# plc_module_xs_00001_001_STM32.net
KiCad netlist of a schematic drawn in Altium Designer
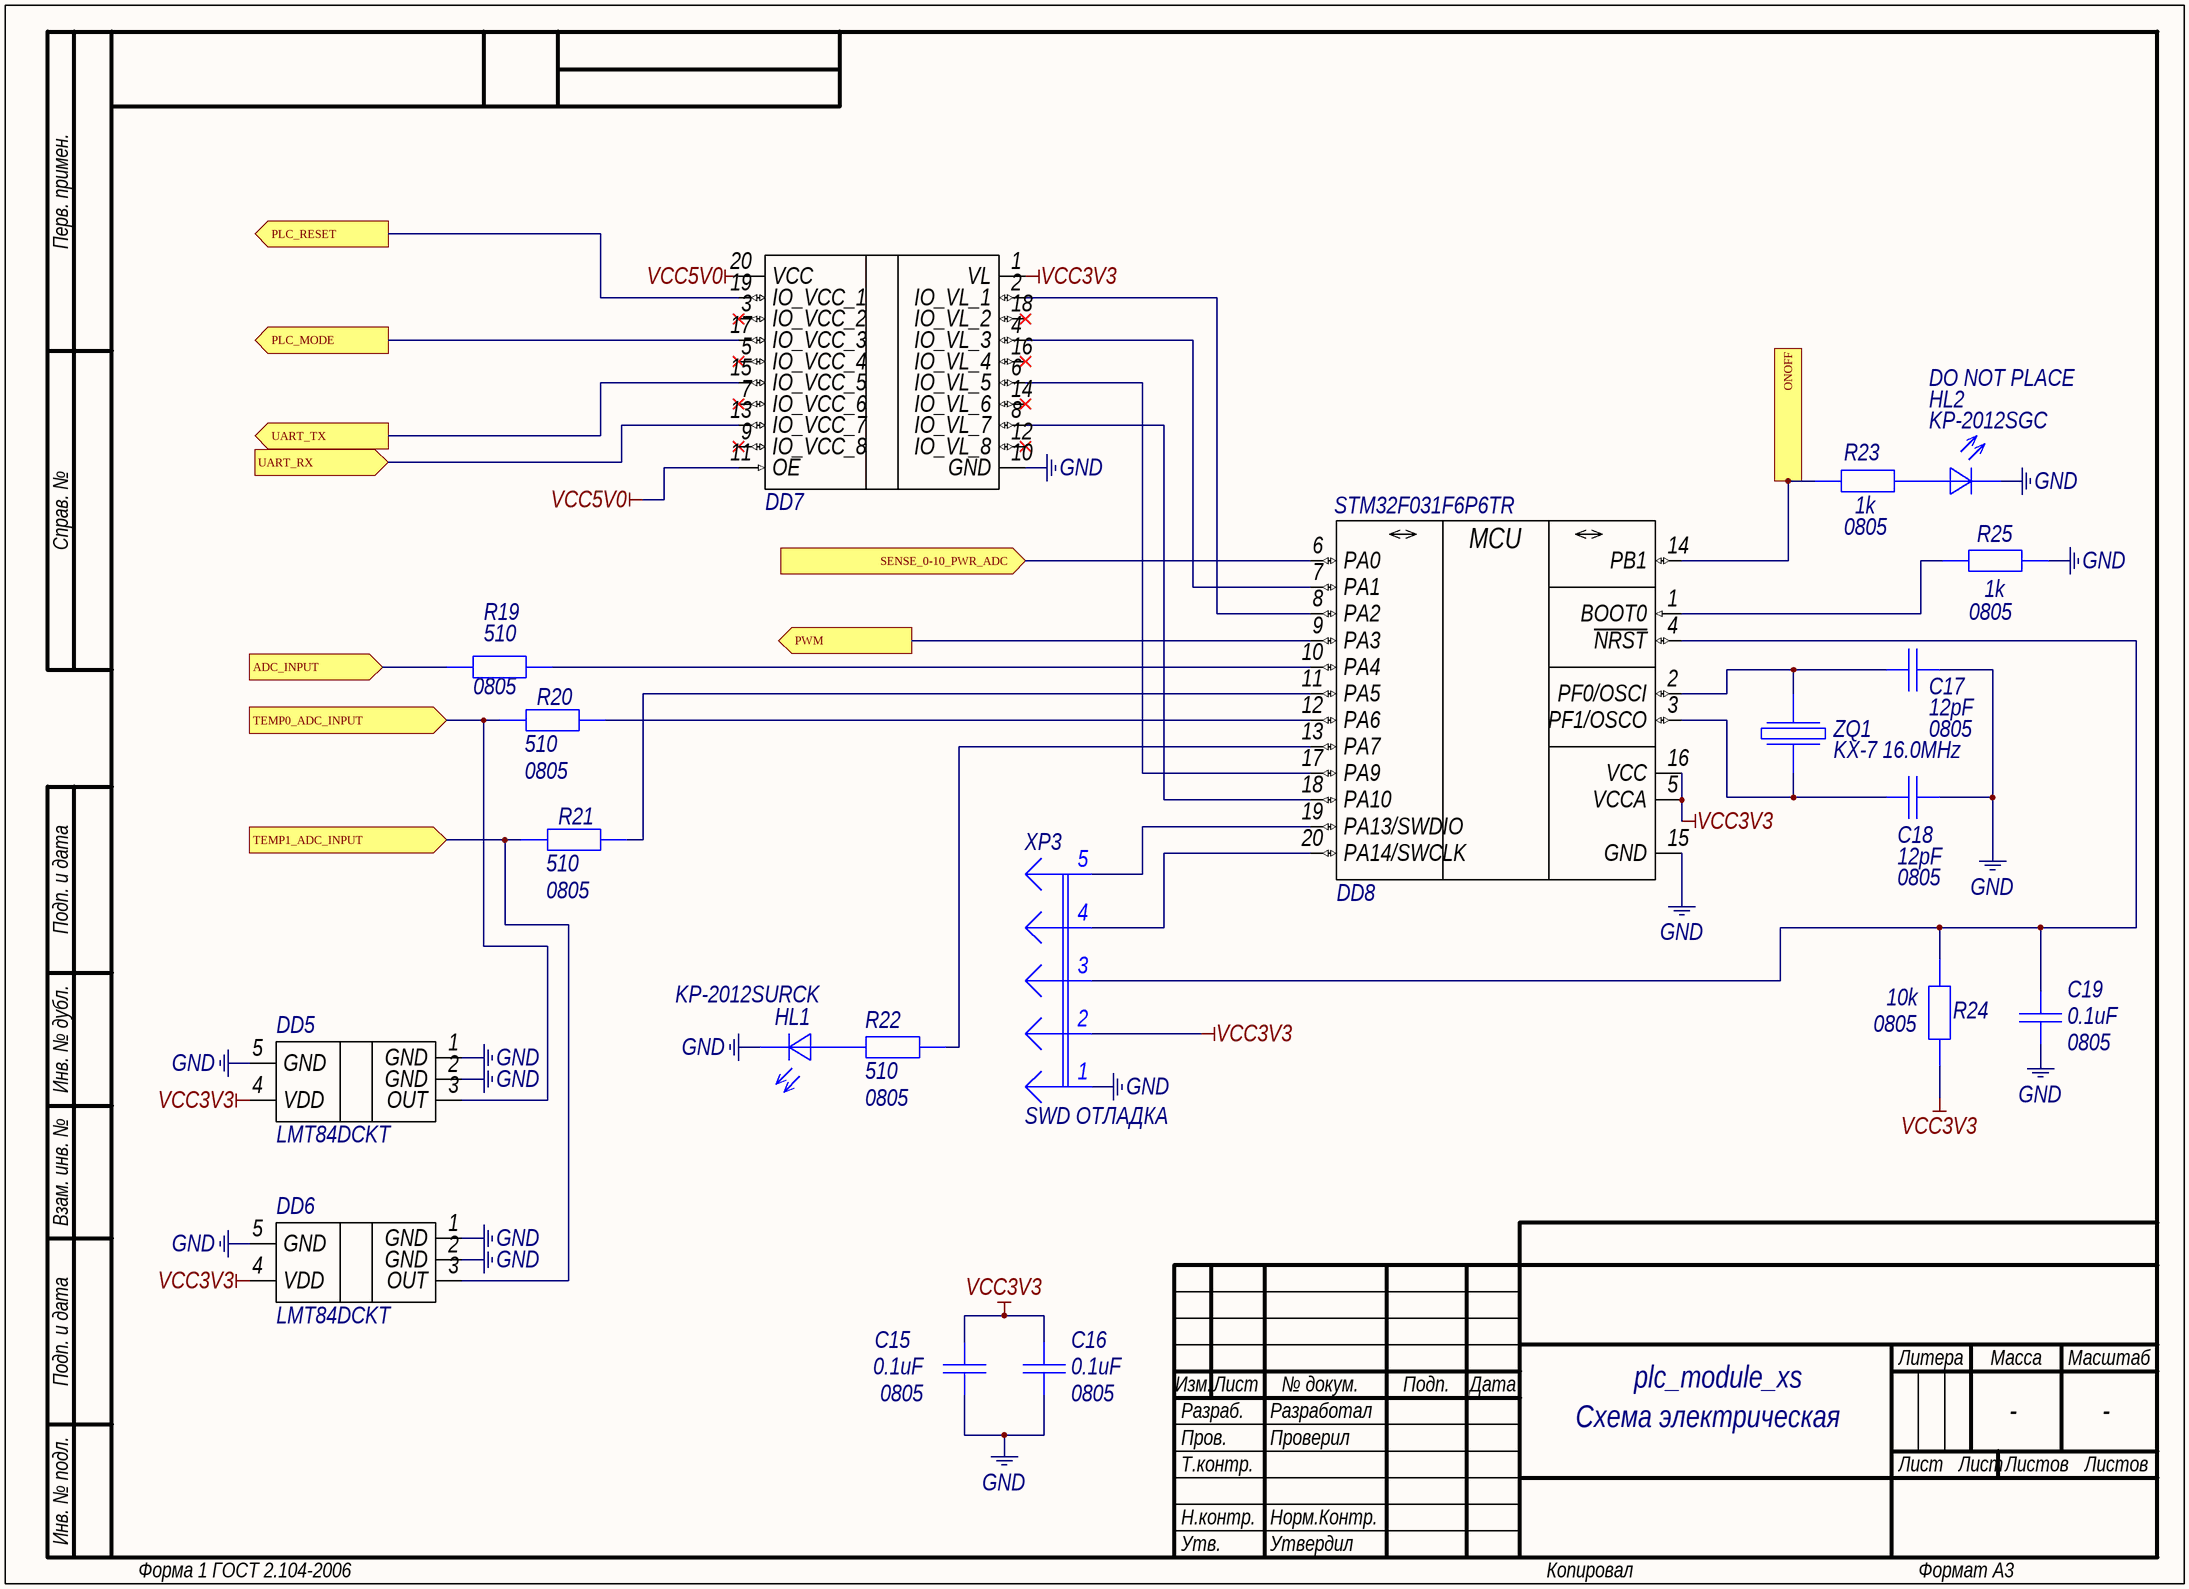
[diagram p0: plc_module_xs.00001.001_STM32.SchDoc]

(export (version "E")
  (design (tool "Eeschema 10.0.6"))
  (components
    (comp (ref "C15")
      (value "0.1uF")
      (footprint "0805")
      (fields
        (field (name "PART NUMBER") "GRM21BR71H104KA01L")
        (field (name "VOLTAGE") "50V")
        (field (name "TOLERANCE") "±10%")
        (field (name "PUBLISHER") "Andrew Danich")
      )
      (libsource (lib "GOST_IMPORT_PARTS") (part "Capacitor"))
    )
    (comp (ref "C16")
      (value "0.1uF")
      (footprint "0805")
      (fields
        (field (name "PART NUMBER") "GRM21BR71H104KA01L")
        (field (name "VOLTAGE") "50V")
        (field (name "TOLERANCE") "±10%")
        (field (name "PUBLISHER") "Andrew Danich")
      )
      (libsource (lib "GOST_IMPORT_PARTS") (part "Capacitor"))
    )
    (comp (ref "C17")
      (value "12pF")
      (footprint "0805")
      (fields
        (field (name "PART NUMBER") "CC0805JRNPO9BN120")
        (field (name "VOLTAGE") "50V")
        (field (name "TOLERANCE") "±5%")
        (field (name "PUBLISHER") "Andrew Danich")
      )
      (libsource (lib "GOST_IMPORT_PARTS") (part "Capacitor"))
    )
    (comp (ref "C18")
      (value "12pF")
      (footprint "0805")
      (fields
        (field (name "PART NUMBER") "CC0805JRNPO9BN120")
        (field (name "VOLTAGE") "50V")
        (field (name "TOLERANCE") "±5%")
        (field (name "PUBLISHER") "Andrew Danich")
      )
      (libsource (lib "GOST_IMPORT_PARTS") (part "Capacitor"))
    )
    (comp (ref "C19")
      (value "0.1uF")
      (footprint "0805")
      (fields
        (field (name "PART NUMBER") "GRM21BR71H104KA01L")
        (field (name "VOLTAGE") "50V")
        (field (name "TOLERANCE") "±10%")
        (field (name "PUBLISHER") "Andrew Danich")
      )
      (libsource (lib "GOST_IMPORT_PARTS") (part "Capacitor"))
    )
    (comp (ref "DD5")
      (value "LMT84DCKT")
      (footprint "SOT65P210X110-5N")
      (description "LMT84/LMT84-Q1 1.5V, SC70/TO-92/TO-126,Analog Temperature Sensors with Class-AB Output")
      (fields (field (name "MANUFACTURER") "Texas Instruments"))
      (libsource (lib "GOST_IMPORT_PARTS") (part "LMT84DCKT"))
    )
    (comp (ref "DD6")
      (value "LMT84DCKT")
      (footprint "SOT65P210X110-5N")
      (description "LMT84/LMT84-Q1 1.5V, SC70/TO-92/TO-126,Analog Temperature Sensors with Class-AB Output")
      (fields (field (name "MANUFACTURER") "Texas Instruments"))
      (libsource (lib "GOST_IMPORT_PARTS") (part "LMT84DCKT"))
    )
    (comp (ref "DD7")
      (value "ST2378ETTR")
      (footprint "SOP65P640X120-20N")
      (description "8-bit dual supply 1.71 V to 5.5 V level translator with I/O VCC ±15 kV ESD protection")
      (fields (field (name "MANUFACTURER") "STMicroelectronics") (field (name "PUBLISHER") "Andrew Danich"))
      (libsource (lib "GOST_IMPORT_PARTS") (part "ST2378ETTR"))
    )
    (comp (ref "DD8")
      (value "STM32F031F6P6TR")
      (footprint "STM-TSSOP20_N")
      (fields (field (name "MANUFACTURER") "STMicroelectronics") (field (name "PUBLISHER") "Andrew Danich"))
      (libsource (lib "GOST_IMPORT_PARTS") (part "STM32F031Fxxx-Series"))
    )
    (comp (ref "HL1")
      (value "KP-2012SURCK")
      (footprint "LD0805")
      (fields (field (name "MANUFACTURER") "Kingbright") (field (name "PUBLISHER") "Andrew Danich"))
      (libsource (lib "GOST_IMPORT_PARTS") (part "Led-1"))
    )
    (comp (ref "HL2")
      (value "DO NOT PLACE")
      (footprint "LD0805")
      (fields
        (field (name "PART NUMBER") "KP-2012SGC")
        (field (name "MANUFACTURER") "Kingbright")
        (field (name "PUBLISHER") "Andrew Danich")
      )
      (libsource (lib "GOST_IMPORT_PARTS") (part "Led-1"))
    )
    (comp (ref "R19")
      (value "510")
      (footprint "0805")
      (fields
        (field (name "PART NUMBER") "RC0805JR-07510RL")
        (field (name "TOLERANCE") "±5%")
        (field (name "MANUFACTURER") "Yageo")
        (field (name "PUBLISHER") "Andrew Danich")
      )
      (libsource (lib "GOST_IMPORT_PARTS") (part "Resistor"))
    )
    (comp (ref "R20")
      (value "510")
      (footprint "0805")
      (fields
        (field (name "PART NUMBER") "RC0805JR-07510RL")
        (field (name "TOLERANCE") "±5%")
        (field (name "MANUFACTURER") "Yageo")
        (field (name "PUBLISHER") "Andrew Danich")
      )
      (libsource (lib "GOST_IMPORT_PARTS") (part "Resistor"))
    )
    (comp (ref "R21")
      (value "510")
      (footprint "0805")
      (fields
        (field (name "PART NUMBER") "RC0805JR-07510RL")
        (field (name "TOLERANCE") "±5%")
        (field (name "MANUFACTURER") "Yageo")
        (field (name "PUBLISHER") "Andrew Danich")
      )
      (libsource (lib "GOST_IMPORT_PARTS") (part "Resistor"))
    )
    (comp (ref "R22")
      (value "510")
      (footprint "0805")
      (fields
        (field (name "PART NUMBER") "RC0805JR-07510RL")
        (field (name "TOLERANCE") "±5%")
        (field (name "MANUFACTURER") "Yageo")
        (field (name "PUBLISHER") "Andrew Danich")
      )
      (libsource (lib "GOST_IMPORT_PARTS") (part "Resistor"))
    )
    (comp (ref "R23")
      (value "1k")
      (footprint "0805")
      (fields
        (field (name "PART NUMBER") "RC0805JR-071KL")
        (field (name "TOLERANCE") "±5%")
        (field (name "MANUFACTURER") "Yageo")
        (field (name "PUBLISHER") "Andrew Danich")
      )
      (libsource (lib "GOST_IMPORT_PARTS") (part "Resistor"))
    )
    (comp (ref "R24")
      (value "10k")
      (footprint "0805")
      (fields
        (field (name "PART NUMBER") "RC0805JR-0710KL")
        (field (name "TOLERANCE") "±5%")
        (field (name "MANUFACTURER") "Yageo")
        (field (name "PUBLISHER") "Andrew Danich")
      )
      (libsource (lib "GOST_IMPORT_PARTS") (part "Resistor"))
    )
    (comp (ref "R25")
      (value "1k")
      (footprint "0805")
      (fields
        (field (name "PART NUMBER") "RC0805JR-071KL")
        (field (name "TOLERANCE") "±5%")
        (field (name "MANUFACTURER") "Yageo")
        (field (name "PUBLISHER") "Andrew Danich")
      )
      (libsource (lib "GOST_IMPORT_PARTS") (part "Resistor"))
    )
    (comp (ref "XP3")
      (value "SWD ОТЛАДКА")
      (footprint "PLS-5")
      (fields (field (name "PART NUMBER") "PLS-5") (field (name "PUBLISHER") "Andrew Danich"))
      (libsource (lib "GOST_IMPORT_PARTS") (part "Con-5-M"))
    )
    (comp (ref "ZQ1")
      (value "KX-7 16.0MHz")
      (footprint "SMD 3.2x2.5mm")
      (fields
        (field (name "MANUFACTURER") "GEYER ELECTRONIC")
        (field (name "Comment") "Crystal-1_3p")
        (field (name "PUBLISHER") "Andrew Danich")
      )
      (libsource (lib "GOST_IMPORT_PARTS") (part "Crystal-1_3p"))
    )
  )
  (nets
    (net (code "1") (name "/ADC_INPUT") (class "Default")
      (node (ref "R19") (pin "2") (pinfunction "2_2") (pintype "passive"))
    )
    (net (code "2") (name "/ONOFF") (class "Default")
      (node (ref "DD8") (pin "14") (pinfunction "PB1_14") (pintype "bidirectional"))
      (node (ref "R23") (pin "1") (pinfunction "1_1") (pintype "passive"))
    )
    (net (code "3") (name "/PLC_MODE") (class "Default")
      (node (ref "DD7") (pin "17") (pinfunction "IO_VCC_3_17") (pintype "bidirectional"))
    )
    (net (code "4") (name "/PLC_RESET") (class "Default")
      (node (ref "DD7") (pin "19") (pinfunction "IO_VCC_1_19") (pintype "bidirectional"))
    )
    (net (code "5") (name "/PWM") (class "Default")
      (node (ref "DD8") (pin "9") (pinfunction "PA3_9") (pintype "bidirectional"))
    )
    (net (code "6") (name "/SENSE_0-10_PWR_ADC") (class "Default")
      (node (ref "DD8") (pin "6") (pinfunction "PA0_6") (pintype "bidirectional"))
    )
    (net (code "7") (name "/TEMP0_ADC_INPUT") (class "Default")
      (node (ref "DD5") (pin "3") (pinfunction "OUT_3") (pintype "passive"))
      (node (ref "R20") (pin "2") (pinfunction "2_2") (pintype "passive"))
    )
    (net (code "8") (name "/TEMP1_ADC_INPUT") (class "Default")
      (node (ref "DD6") (pin "3") (pinfunction "OUT_3") (pintype "passive"))
      (node (ref "R21") (pin "2") (pinfunction "2_2") (pintype "passive"))
    )
    (net (code "9") (name "/UART_RX") (class "Default")
      (node (ref "DD7") (pin "13") (pinfunction "IO_VCC_7_13") (pintype "bidirectional"))
    )
    (net (code "10") (name "/UART_TX") (class "Default")
      (node (ref "DD7") (pin "15") (pinfunction "IO_VCC_5_15") (pintype "bidirectional"))
    )
    (net (code "11") (name "GND") (class "Default")
      (node (ref "C15") (pin "2") (pinfunction "2_2") (pintype "passive"))
      (node (ref "C16") (pin "1") (pinfunction "1_1") (pintype "passive"))
      (node (ref "C17") (pin "1") (pinfunction "1_1") (pintype "passive"))
      (node (ref "C18") (pin "1") (pinfunction "1_1") (pintype "passive"))
      (node (ref "C19") (pin "1") (pinfunction "1_1") (pintype "passive"))
      (node (ref "DD5") (pin "1") (pinfunction "GND_1") (pintype "passive"))
      (node (ref "DD5") (pin "2") (pinfunction "GND_2") (pintype "passive"))
      (node (ref "DD5") (pin "5") (pinfunction "GND_5") (pintype "passive"))
      (node (ref "DD6") (pin "1") (pinfunction "GND_1") (pintype "passive"))
      (node (ref "DD6") (pin "2") (pinfunction "GND_2") (pintype "passive"))
      (node (ref "DD6") (pin "5") (pinfunction "GND_5") (pintype "passive"))
      (node (ref "DD7") (pin "10") (pinfunction "GND_10") (pintype "power_in"))
      (node (ref "DD8") (pin "15") (pinfunction "GND_15") (pintype "power_in"))
      (node (ref "HL1") (pin "2") (pinfunction "К_2") (pintype "passive"))
      (node (ref "HL2") (pin "2") (pinfunction "К_2") (pintype "passive"))
      (node (ref "R25") (pin "2") (pinfunction "2_2") (pintype "passive"))
      (node (ref "XP3") (pin "1") (pintype "passive"))
    )
    (net (code "12") (name "Net-(DD7-IO_VL_1)") (class "Default")
      (node (ref "DD7") (pin "2") (pinfunction "IO_VL_1_2") (pintype "bidirectional"))
      (node (ref "DD8") (pin "8") (pinfunction "PA2_8") (pintype "bidirectional"))
    )
    (net (code "13") (name "Net-(DD7-IO_VL_3)") (class "Default")
      (node (ref "DD7") (pin "4") (pinfunction "IO_VL_3_4") (pintype "bidirectional"))
      (node (ref "DD8") (pin "7") (pinfunction "PA1_7") (pintype "bidirectional"))
    )
    (net (code "14") (name "Net-(DD7-IO_VL_5)") (class "Default")
      (node (ref "DD7") (pin "6") (pinfunction "IO_VL_5_6") (pintype "bidirectional"))
      (node (ref "DD8") (pin "17") (pinfunction "PA9_17") (pintype "bidirectional"))
    )
    (net (code "15") (name "Net-(DD7-IO_VL_7)") (class "Default")
      (node (ref "DD7") (pin "8") (pinfunction "IO_VL_7_8") (pintype "bidirectional"))
      (node (ref "DD8") (pin "18") (pinfunction "PA10_18") (pintype "bidirectional"))
    )
    (net (code "16") (name "Net-(DD8-BOOT0)") (class "Default")
      (node (ref "DD8") (pin "1") (pinfunction "BOOT0_1") (pintype "input"))
      (node (ref "R25") (pin "1") (pinfunction "1_1") (pintype "passive"))
    )
    (net (code "17") (name "Net-(DD8-PA4)") (class "Default")
      (node (ref "DD8") (pin "10") (pinfunction "PA4_10") (pintype "bidirectional"))
      (node (ref "R19") (pin "1") (pinfunction "1_1") (pintype "passive"))
    )
    (net (code "18") (name "Net-(DD8-PA5)") (class "Default")
      (node (ref "DD8") (pin "11") (pinfunction "PA5_11") (pintype "bidirectional"))
      (node (ref "R21") (pin "1") (pinfunction "1_1") (pintype "passive"))
    )
    (net (code "19") (name "Net-(DD8-PA6)") (class "Default")
      (node (ref "DD8") (pin "12") (pinfunction "PA6_12") (pintype "bidirectional"))
      (node (ref "R20") (pin "1") (pinfunction "1_1") (pintype "passive"))
    )
    (net (code "20") (name "Net-(DD8-PA7)") (class "Default")
      (node (ref "DD8") (pin "13") (pinfunction "PA7_13") (pintype "bidirectional"))
      (node (ref "R22") (pin "1") (pinfunction "1_1") (pintype "passive"))
    )
    (net (code "21") (name "Net-(DD8-PA13{slash}SWDIO)") (class "Default")
      (node (ref "DD8") (pin "19") (pinfunction "PA13/SWDIO_19") (pintype "bidirectional"))
      (node (ref "XP3") (pin "5") (pintype "passive"))
    )
    (net (code "22") (name "Net-(DD8-PA14{slash}SWCLK)") (class "Default")
      (node (ref "DD8") (pin "20") (pinfunction "PA14/SWCLK_20") (pintype "bidirectional"))
      (node (ref "XP3") (pin "4") (pintype "passive"))
    )
    (net (code "23") (name "Net-(DD8-PF0{slash}OSCI)") (class "Default")
      (node (ref "C17") (pin "2") (pinfunction "2_2") (pintype "passive"))
      (node (ref "DD8") (pin "2") (pinfunction "PF0/OSCI_2") (pintype "bidirectional"))
      (node (ref "ZQ1") (pin "3") (pinfunction "3_3") (pintype "passive"))
    )
    (net (code "24") (name "Net-(DD8-PF1{slash}OSCO)") (class "Default")
      (node (ref "C18") (pin "2") (pinfunction "2_2") (pintype "passive"))
      (node (ref "DD8") (pin "3") (pinfunction "PF1/OSCO_3") (pintype "bidirectional"))
      (node (ref "ZQ1") (pin "1") (pinfunction "1_1") (pintype "passive"))
    )
    (net (code "25") (name "Net-(DD8-~{NRST})") (class "Default")
      (node (ref "C19") (pin "2") (pinfunction "2_2") (pintype "passive"))
      (node (ref "DD8") (pin "4") (pinfunction "~{NRST}_4") (pintype "bidirectional"))
      (node (ref "R24") (pin "2") (pinfunction "2_2") (pintype "passive"))
      (node (ref "XP3") (pin "3") (pintype "passive"))
    )
    (net (code "26") (name "Net-(HL1-А)") (class "Default")
      (node (ref "HL1") (pin "1") (pinfunction "А_1") (pintype "passive"))
      (node (ref "R22") (pin "2") (pinfunction "2_2") (pintype "passive"))
    )
    (net (code "27") (name "Net-(HL2-А)") (class "Default")
      (node (ref "HL2") (pin "1") (pinfunction "А_1") (pintype "passive"))
      (node (ref "R23") (pin "2") (pinfunction "2_2") (pintype "passive"))
    )
    (net (code "28") (name "VCC3V3") (class "Default")
      (node (ref "C15") (pin "1") (pinfunction "1_1") (pintype "passive"))
      (node (ref "C16") (pin "2") (pinfunction "2_2") (pintype "passive"))
      (node (ref "DD5") (pin "4") (pinfunction "VDD_4") (pintype "passive"))
      (node (ref "DD6") (pin "4") (pinfunction "VDD_4") (pintype "passive"))
      (node (ref "DD7") (pin "1") (pinfunction "VL_1") (pintype "power_in"))
      (node (ref "DD8") (pin "16") (pinfunction "VCC_16") (pintype "power_in"))
      (node (ref "DD8") (pin "5") (pinfunction "VCCA_5") (pintype "power_in"))
      (node (ref "R24") (pin "1") (pinfunction "1_1") (pintype "passive"))
      (node (ref "XP3") (pin "2") (pintype "passive"))
    )
    (net (code "29") (name "VCC5V0") (class "Default")
      (node (ref "DD7") (pin "11") (pinfunction "OE_11") (pintype "input"))
      (node (ref "DD7") (pin "20") (pinfunction "VCC_20") (pintype "power_in"))
    )
    (net (code "30") (name "unconnected-(DD7-IO_VCC_2-Pad3)") (class "Default")
      (node (ref "DD7") (pin "3") (pinfunction "IO_VCC_2_3") (pintype "bidirectional+no_connect"))
    )
    (net (code "31") (name "unconnected-(DD7-IO_VCC_4-Pad5)") (class "Default")
      (node (ref "DD7") (pin "5") (pinfunction "IO_VCC_4_5") (pintype "bidirectional+no_connect"))
    )
    (net (code "32") (name "unconnected-(DD7-IO_VCC_6-Pad7)") (class "Default")
      (node (ref "DD7") (pin "7") (pinfunction "IO_VCC_6_7") (pintype "bidirectional+no_connect"))
    )
    (net (code "33") (name "unconnected-(DD7-IO_VCC_8-Pad9)") (class "Default")
      (node (ref "DD7") (pin "9") (pinfunction "IO_VCC_8_9") (pintype "bidirectional+no_connect"))
    )
    (net (code "34") (name "unconnected-(DD7-IO_VL_2-Pad18)") (class "Default")
      (node (ref "DD7") (pin "18") (pinfunction "IO_VL_2_18") (pintype "bidirectional+no_connect"))
    )
    (net (code "35") (name "unconnected-(DD7-IO_VL_4-Pad16)") (class "Default")
      (node (ref "DD7") (pin "16") (pinfunction "IO_VL_4_16") (pintype "bidirectional+no_connect"))
    )
    (net (code "36") (name "unconnected-(DD7-IO_VL_6-Pad14)") (class "Default")
      (node (ref "DD7") (pin "14") (pinfunction "IO_VL_6_14") (pintype "bidirectional+no_connect"))
    )
    (net (code "37") (name "unconnected-(DD7-IO_VL_8-Pad12)") (class "Default")
      (node (ref "DD7") (pin "12") (pinfunction "IO_VL_8_12") (pintype "bidirectional+no_connect"))
    )
  )
)
